# Coil.net
KiCad netlist of a schematic drawn in Altium Designer
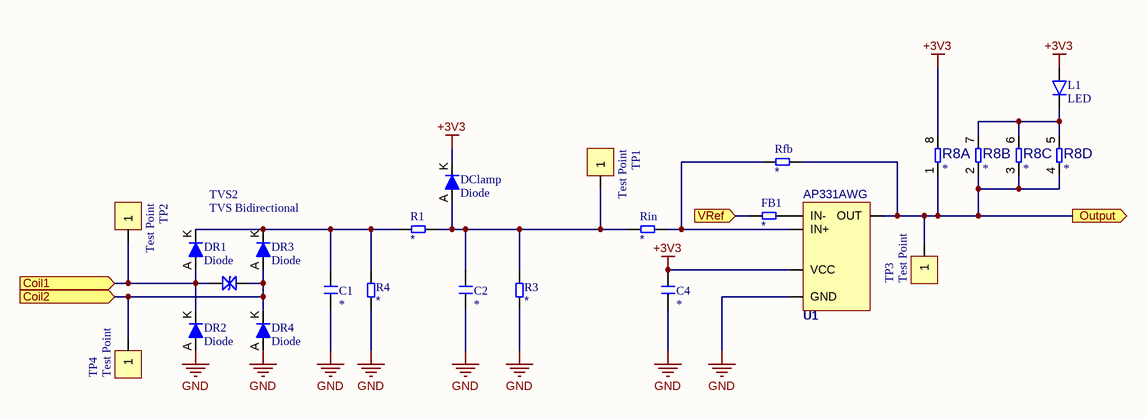
[diagram p0: Coil.SchDoc]

(export (version "E")
  (design (tool "Eeschema 10.0.6"))
  (components
    (comp (ref "C1")
      (value "*")
      (footprint "C0603_N")
      (description "Capacitor MLCC")
      (fields
        (field (name "MANUFACTURER") "Yageo")
        (field (name "MANUFACTURER PART NUMBER") "CC0603KRX7R9BB104")
      )
      (libsource (lib "wes") (part "Capacitor"))
    )
    (comp (ref "C2")
      (value "*")
      (footprint "C0603_N")
      (description "Capacitor MLCC")
      (fields
        (field (name "MANUFACTURER") "Yageo")
        (field (name "MANUFACTURER PART NUMBER") "CC0603KRX7R9BB104")
      )
      (libsource (lib "wes") (part "Capacitor"))
    )
    (comp (ref "C4")
      (value "*")
      (footprint "C0603_N")
      (description "Capacitor MLCC")
      (fields
        (field (name "MANUFACTURER") "Yageo")
        (field (name "MANUFACTURER PART NUMBER") "CC0603KRX7R9BB104")
      )
      (libsource (lib "wes") (part "Capacitor"))
    )
    (comp (ref "DClamp") (value "Diode") (footprint "SOD323F") (libsource (lib "wes") (part "Diode")))
    (comp (ref "DR1") (value "Diode") (footprint "SOD323F") (libsource (lib "wes") (part "Diode")))
    (comp (ref "DR2") (value "Diode") (footprint "SOD323F") (libsource (lib "wes") (part "Diode")))
    (comp (ref "DR3") (value "Diode") (footprint "SOD323F") (libsource (lib "wes") (part "Diode")))
    (comp (ref "DR4") (value "Diode") (footprint "SOD323F") (libsource (lib "wes") (part "Diode")))
    (comp (ref "FB1")
      (value "Resistor")
      (footprint "R0603")
      (fields (field (name "ALTIUM_VALUE") "*") (field (name "PUBLISHER") "Altium Limited"))
      (libsource (lib "wes") (part "Resistor"))
    )
    (comp (ref "L1") (value "LED") (footprint "LED 0603/1608") (libsource (lib "wes") (part "LED")))
    (comp (ref "R1")
      (value "Resistor")
      (footprint "R0603")
      (fields (field (name "ALTIUM_VALUE") "*") (field (name "PUBLISHER") "Altium Limited"))
      (libsource (lib "wes") (part "Resistor"))
    )
    (comp (ref "R3")
      (value "Resistor")
      (footprint "R0603")
      (fields (field (name "ALTIUM_VALUE") "*") (field (name "PUBLISHER") "Altium Limited"))
      (libsource (lib "wes") (part "Resistor"))
    )
    (comp (ref "R4")
      (value "Resistor")
      (footprint "R0603")
      (fields (field (name "ALTIUM_VALUE") "*") (field (name "PUBLISHER") "Altium Limited"))
      (libsource (lib "wes") (part "Resistor"))
    )
    (comp (ref "R8")
      (value "Resistor Array - 4P")
      (footprint "YC164")
      (fields (field (name "ALTIUM_VALUE") "*"))
      (libsource (lib "wes") (part "Resistor Array - 4P"))
    )
    (comp (ref "Rfb")
      (value "Resistor")
      (footprint "R0603")
      (fields (field (name "ALTIUM_VALUE") "*") (field (name "PUBLISHER") "Altium Limited"))
      (libsource (lib "wes") (part "Resistor"))
    )
    (comp (ref "Rin")
      (value "Resistor")
      (footprint "R0603")
      (fields (field (name "ALTIUM_VALUE") "*") (field (name "PUBLISHER") "Altium Limited"))
      (libsource (lib "wes") (part "Resistor"))
    )
    (comp (ref "TP1")
      (value "Test Point")
      (footprint "Harwin S2751-46R")
      (libsource (lib "") (part "Test Point_1"))
    )
    (comp (ref "TP2")
      (value "Test Point")
      (footprint "Harwin S2751-46R")
      (libsource (lib "") (part "Test Point_1"))
    )
    (comp (ref "TP3")
      (value "Test Point")
      (footprint "Harwin S2751-46R")
      (libsource (lib "wes") (part "Test Point"))
    )
    (comp (ref "TP4")
      (value "Test Point")
      (footprint "Harwin S2751-46R")
      (libsource (lib "wes") (part "Test Point"))
    )
    (comp (ref "TVS2")
      (value "TVS Bidirectional")
      (footprint "SOD323F-Comchip Variant")
      (libsource (lib "wes") (part "TVS Bidirectional"))
    )
    (comp (ref "U1") (value "AP331AWG") (footprint "SOT23-5_N") (libsource (lib "wes") (part "AP331AWG")))
  )
  (nets
    (net (code "1") (name "+3V3") (class "Default")
      (node (ref "C4") (pin "1") (pintype "passive"))
      (node (ref "DClamp") (pin "K") (pinfunction "K_K") (pintype "passive"))
      (node (ref "L1") (pin "2") (pinfunction "A_2") (pintype "power_in"))
      (node (ref "R8") (pin "8") (pinfunction "8_8") (pintype "passive"))
      (node (ref "U1") (pin "5") (pinfunction "VCC_5") (pintype "passive"))
    )
    (net (code "2") (name "/Coil1") (class "Default")
      (node (ref "DR1") (pin "A") (pinfunction "A_A") (pintype "passive"))
      (node (ref "DR2") (pin "K") (pinfunction "K_K") (pintype "passive"))
      (node (ref "TP2") (pin "1") (pinfunction "1_1") (pintype "passive"))
      (node (ref "TVS2") (pin "2") (pinfunction "2_2") (pintype "passive"))
    )
    (net (code "3") (name "/Coil2") (class "Default")
      (node (ref "DR3") (pin "A") (pinfunction "A_A") (pintype "passive"))
      (node (ref "DR4") (pin "K") (pinfunction "K_K") (pintype "passive"))
      (node (ref "TP4") (pin "1") (pinfunction "1_1") (pintype "passive"))
      (node (ref "TVS2") (pin "1") (pinfunction "1_1") (pintype "passive"))
    )
    (net (code "4") (name "/Output") (class "Default")
      (node (ref "R8") (pin "1") (pinfunction "1_1") (pintype "passive"))
      (node (ref "R8") (pin "2") (pinfunction "2_2") (pintype "passive"))
      (node (ref "R8") (pin "3") (pinfunction "3_3") (pintype "passive"))
      (node (ref "R8") (pin "4") (pinfunction "4_4") (pintype "passive"))
      (node (ref "Rfb") (pin "2") (pinfunction "2_2") (pintype "passive"))
      (node (ref "TP3") (pin "1") (pinfunction "1_1") (pintype "passive"))
      (node (ref "U1") (pin "4") (pinfunction "OUT_4") (pintype "passive"))
    )
    (net (code "5") (name "/VRef") (class "Default")
      (node (ref "FB1") (pin "1") (pinfunction "1_1") (pintype "passive"))
    )
    (net (code "6") (name "GND") (class "Default")
      (node (ref "C1") (pin "2") (pintype "passive"))
      (node (ref "C2") (pin "2") (pintype "passive"))
      (node (ref "C4") (pin "2") (pintype "passive"))
      (node (ref "DR2") (pin "A") (pinfunction "A_A") (pintype "passive"))
      (node (ref "DR4") (pin "A") (pinfunction "A_A") (pintype "passive"))
      (node (ref "R3") (pin "1") (pinfunction "1_1") (pintype "passive"))
      (node (ref "R4") (pin "1") (pinfunction "1_1") (pintype "passive"))
      (node (ref "U1") (pin "2") (pinfunction "GND_2") (pintype "passive"))
    )
    (net (code "7") (name "Net-(C1-Pad1)") (class "Default")
      (node (ref "C1") (pin "1") (pintype "passive"))
      (node (ref "DR1") (pin "K") (pinfunction "K_K") (pintype "passive"))
      (node (ref "DR3") (pin "K") (pinfunction "K_K") (pintype "passive"))
      (node (ref "R1") (pin "1") (pinfunction "1_1") (pintype "passive"))
      (node (ref "R4") (pin "2") (pinfunction "2_2") (pintype "passive"))
    )
    (net (code "8") (name "Net-(C2-Pad1)") (class "Default")
      (node (ref "C2") (pin "1") (pintype "passive"))
      (node (ref "DClamp") (pin "A") (pinfunction "A_A") (pintype "passive"))
      (node (ref "R1") (pin "2") (pinfunction "2_2") (pintype "passive"))
      (node (ref "R3") (pin "2") (pinfunction "2_2") (pintype "passive"))
      (node (ref "Rin") (pin "1") (pinfunction "1_1") (pintype "passive"))
      (node (ref "TP1") (pin "1") (pinfunction "1_1") (pintype "passive"))
    )
    (net (code "9") (name "Net-(L1-K)") (class "Default")
      (node (ref "L1") (pin "1") (pinfunction "K_1") (pintype "power_in"))
      (node (ref "R8") (pin "5") (pinfunction "5_5") (pintype "passive"))
      (node (ref "R8") (pin "6") (pinfunction "6_6") (pintype "passive"))
      (node (ref "R8") (pin "7") (pinfunction "7_7") (pintype "passive"))
    )
    (net (code "10") (name "Net-(U1-IN+)") (class "Default")
      (node (ref "Rfb") (pin "1") (pinfunction "1_1") (pintype "passive"))
      (node (ref "Rin") (pin "2") (pinfunction "2_2") (pintype "passive"))
      (node (ref "U1") (pin "3") (pinfunction "IN+_3") (pintype "passive"))
    )
    (net (code "11") (name "Net-(U1-IN-)") (class "Default")
      (node (ref "FB1") (pin "2") (pinfunction "2_2") (pintype "passive"))
      (node (ref "U1") (pin "1") (pinfunction "IN-_1") (pintype "passive"))
    )
  )
)
